# SENSORS_FMU_REV_1B.net
KiCad netlist of a schematic drawn in Altium Designer
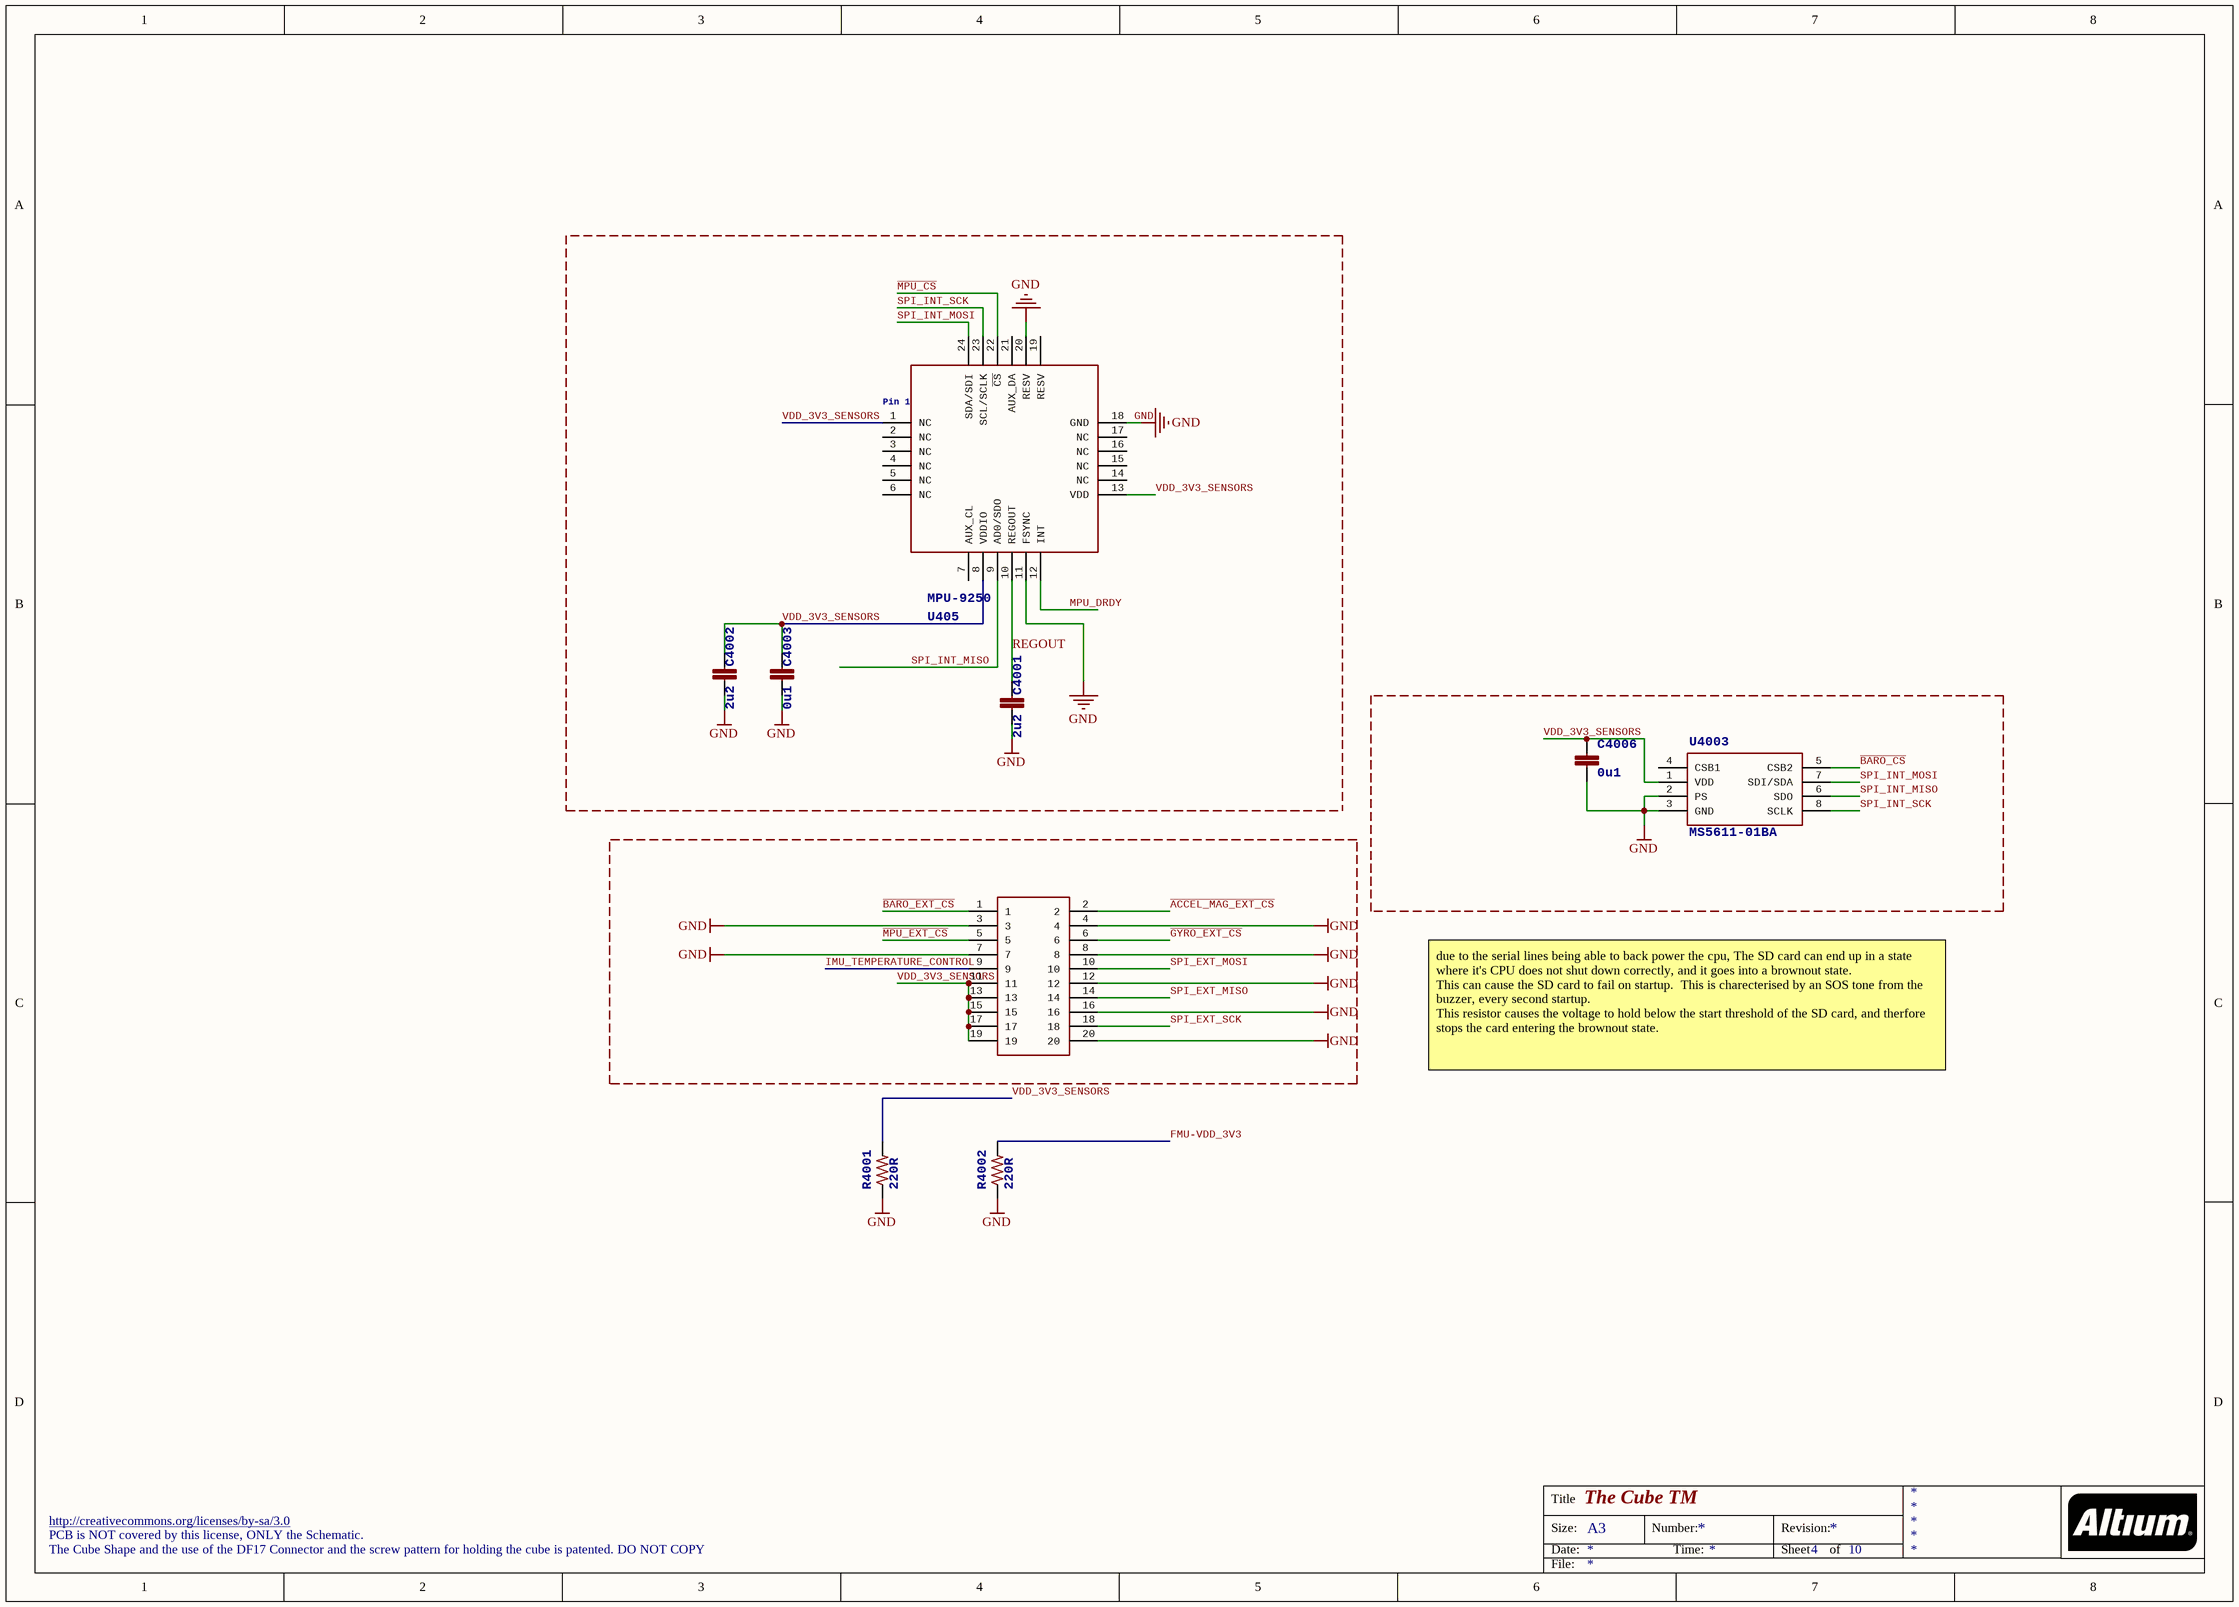
[diagram p0: SENSORS_FMU_REV_1B.SchDoc]

(export (version "E")
  (design (tool "Eeschema 10.0.6"))
  (components
    (comp (ref "C4001")
      (value "2u2")
      (footprint "0603-CAP")
      (description "CAP CER 2.2UF 16V 10% X6S 0603")
      (libsource (lib "pixhawk2") (part "CAP0603"))
    )
    (comp (ref "C4002")
      (value "2u2")
      (footprint "0603-CAP")
      (description "CAP CER 2.2UF 16V 10% X6S 0603")
      (libsource (lib "pixhawk2") (part "CAP0603"))
    )
    (comp (ref "C4003")
      (value "0u1")
      (footprint "0402-CAP")
      (description "CAP CER 0.1UF 16V Y5V 0402")
      (libsource (lib "pixhawk2") (part "CAP0402"))
    )
    (comp (ref "C4006")
      (value "0u1")
      (footprint "0402-CAP")
      (description "CAP CER 0.1UF 16V Y5V 0402")
      (libsource (lib "pixhawk2") (part "CAP0402"))
    )
    (comp (ref "R4001")
      (value "220R")
      (footprint "0402-RES")
      (description "RES 220 OHM 1/16W 1% 0402 SMD")
      (libsource (lib "pixhawk2") (part "RESISTOR0402-RES"))
    )
    (comp (ref "R4002")
      (value "220R")
      (footprint "0402-RES")
      (description "RES 220 OHM 1/16W 1% 0402 SMD")
      (libsource (lib "pixhawk2") (part "RESISTOR0402-RES"))
    )
    (comp (ref "U$2")
      (value "DF40C-20-DS")
      (footprint "DF-40C-20DS")
      (description "CONN RCPT 20POS 0.4MM SMD GOLD")
      (libsource (lib "pixhawk2") (part "DF40C-20-DS"))
    )
    (comp (ref "U405")
      (value "MPU-9250")
      (footprint "MPU-9250")
      (fields (field (name "PIN 1") "Pin 1"))
      (libsource (lib "pixhawk2") (part "MPU-6500"))
    )
    (comp (ref "U4003")
      (value "MS5611-01BA")
      (footprint "MS5611-01BA")
      (description "Board Mount Pressure Sensors")
      (libsource (lib "pixhawk2") (part "MS5611-01BA"))
    )
  )
  (nets
    (net (code "1") (name "/FMU-VDD_3V3") (class "Default")
      (node (ref "R4002") (pin "P$2") (pinfunction "2_P$2") (pintype "passive"))
    )
    (net (code "2") (name "/IMU_TEMPERATURE_CONTROL") (class "Default")
      (node (ref "U$2") (pin "9") (pinfunction "9_9") (pintype "passive"))
    )
    (net (code "3") (name "/MPU_DRDY") (class "Default")
      (node (ref "U405") (pin "12") (pinfunction "INT_12") (pintype "passive"))
    )
    (net (code "4") (name "/REGOUT") (class "Default")
      (node (ref "C4001") (pin "P$1") (pinfunction "1_P$1") (pintype "passive"))
      (node (ref "U405") (pin "10") (pinfunction "REGOUT_10") (pintype "passive"))
    )
    (net (code "5") (name "/SPI_EXT_MISO") (class "Default")
      (node (ref "U$2") (pin "14") (pinfunction "14_14") (pintype "passive"))
    )
    (net (code "6") (name "/SPI_EXT_MOSI") (class "Default")
      (node (ref "U$2") (pin "10") (pinfunction "10_10") (pintype "passive"))
    )
    (net (code "7") (name "/SPI_EXT_SCK") (class "Default")
      (node (ref "U$2") (pin "18") (pinfunction "18_18") (pintype "passive"))
    )
    (net (code "8") (name "/SPI_INT_MISO") (class "Default")
      (node (ref "U4003") (pin "6") (pinfunction "SDO_6") (pintype "passive"))
      (node (ref "U405") (pin "9") (pinfunction "AD0/SDO_9") (pintype "passive"))
    )
    (net (code "9") (name "/SPI_INT_MOSI") (class "Default")
      (node (ref "U4003") (pin "7") (pinfunction "SDI/SDA_7") (pintype "passive"))
      (node (ref "U405") (pin "24") (pinfunction "SDA/SDI_24") (pintype "passive"))
    )
    (net (code "10") (name "/SPI_INT_SCK") (class "Default")
      (node (ref "U4003") (pin "8") (pinfunction "SCLK_8") (pintype "passive"))
      (node (ref "U405") (pin "23") (pinfunction "SCL/SCLK_23") (pintype "passive"))
    )
    (net (code "11") (name "/VDD_3V3_SENSORS") (class "Default")
      (node (ref "C4002") (pin "P$1") (pinfunction "1_P$1") (pintype "passive"))
      (node (ref "C4003") (pin "P$1") (pinfunction "1_P$1") (pintype "passive"))
      (node (ref "C4006") (pin "P$1") (pinfunction "1_P$1") (pintype "passive"))
      (node (ref "R4001") (pin "P$2") (pinfunction "2_P$2") (pintype "passive"))
      (node (ref "U$2") (pin "11") (pinfunction "11_11") (pintype "passive"))
      (node (ref "U$2") (pin "13") (pinfunction "13_13") (pintype "passive"))
      (node (ref "U$2") (pin "15") (pinfunction "15_15") (pintype "passive"))
      (node (ref "U$2") (pin "17") (pinfunction "17_17") (pintype "passive"))
      (node (ref "U$2") (pin "19") (pinfunction "19_19") (pintype "passive"))
      (node (ref "U4003") (pin "1") (pinfunction "VDD_1") (pintype "passive"))
      (node (ref "U405") (pin "1") (pinfunction "NC_1") (pintype "passive"))
      (node (ref "U405") (pin "13") (pinfunction "VDD_13") (pintype "passive"))
      (node (ref "U405") (pin "8") (pinfunction "VDDIO_8") (pintype "passive"))
    )
    (net (code "12") (name "/~{ACCEL_MAG_EXT_CS}") (class "Default")
      (node (ref "U$2") (pin "2") (pinfunction "2_2") (pintype "passive"))
    )
    (net (code "13") (name "/~{BARO_CS}") (class "Default")
      (node (ref "U4003") (pin "5") (pinfunction "CSB2_5") (pintype "passive"))
    )
    (net (code "14") (name "/~{BARO_EXT_CS}") (class "Default")
      (node (ref "U$2") (pin "1") (pinfunction "1_1") (pintype "passive"))
    )
    (net (code "15") (name "/~{GYRO_EXT_CS}") (class "Default")
      (node (ref "U$2") (pin "6") (pinfunction "6_6") (pintype "passive"))
    )
    (net (code "16") (name "/~{MPU_CS}") (class "Default")
      (node (ref "U405") (pin "22") (pinfunction "~{CS}_22") (pintype "passive"))
    )
    (net (code "17") (name "/~{MPU_EXT_CS}") (class "Default")
      (node (ref "U$2") (pin "5") (pinfunction "5_5") (pintype "passive"))
    )
    (net (code "18") (name "GND") (class "Default")
      (node (ref "C4001") (pin "P$2") (pinfunction "2_P$2") (pintype "passive"))
      (node (ref "C4002") (pin "P$2") (pinfunction "2_P$2") (pintype "passive"))
      (node (ref "C4003") (pin "P$2") (pinfunction "2_P$2") (pintype "passive"))
      (node (ref "C4006") (pin "P$2") (pinfunction "2_P$2") (pintype "passive"))
      (node (ref "R4001") (pin "P$1") (pinfunction "1_P$1") (pintype "passive"))
      (node (ref "R4002") (pin "P$1") (pinfunction "1_P$1") (pintype "passive"))
      (node (ref "U$2") (pin "12") (pinfunction "12_12") (pintype "passive"))
      (node (ref "U$2") (pin "16") (pinfunction "16_16") (pintype "passive"))
      (node (ref "U$2") (pin "20") (pinfunction "20_20") (pintype "passive"))
      (node (ref "U$2") (pin "3") (pinfunction "3_3") (pintype "passive"))
      (node (ref "U$2") (pin "4") (pinfunction "4_4") (pintype "passive"))
      (node (ref "U$2") (pin "7") (pinfunction "7_7") (pintype "passive"))
      (node (ref "U$2") (pin "8") (pinfunction "8_8") (pintype "passive"))
      (node (ref "U4003") (pin "2") (pinfunction "PS_2") (pintype "passive"))
      (node (ref "U4003") (pin "3") (pinfunction "GND_3") (pintype "passive"))
      (node (ref "U405") (pin "11") (pinfunction "FSYNC_11") (pintype "passive"))
      (node (ref "U405") (pin "18") (pinfunction "GND_18") (pintype "passive"))
      (node (ref "U405") (pin "20") (pinfunction "RESV_20") (pintype "passive"))
    )
    (net (code "19") (name "unconnected-(U405-AUX_CL-Pad7)") (class "Default")
      (node (ref "U405") (pin "7") (pinfunction "AUX_CL_7") (pintype "passive"))
    )
    (net (code "20") (name "unconnected-(U405-AUX_DA-Pad21)") (class "Default")
      (node (ref "U405") (pin "21") (pinfunction "AUX_DA_21") (pintype "passive"))
    )
    (net (code "21") (name "unconnected-(U405-NC-Pad2)") (class "Default")
      (node (ref "U405") (pin "2") (pinfunction "NC_2") (pintype "passive"))
    )
    (net (code "22") (name "unconnected-(U405-NC-Pad3)") (class "Default")
      (node (ref "U405") (pin "3") (pinfunction "NC_3") (pintype "passive"))
    )
    (net (code "23") (name "unconnected-(U405-NC-Pad4)") (class "Default")
      (node (ref "U405") (pin "4") (pinfunction "NC_4") (pintype "passive"))
    )
    (net (code "24") (name "unconnected-(U405-NC-Pad5)") (class "Default")
      (node (ref "U405") (pin "5") (pinfunction "NC_5") (pintype "passive"))
    )
    (net (code "25") (name "unconnected-(U405-NC-Pad6)") (class "Default")
      (node (ref "U405") (pin "6") (pinfunction "NC_6") (pintype "passive"))
    )
    (net (code "26") (name "unconnected-(U405-NC-Pad14)") (class "Default")
      (node (ref "U405") (pin "14") (pinfunction "NC_14") (pintype "passive"))
    )
    (net (code "27") (name "unconnected-(U405-NC-Pad15)") (class "Default")
      (node (ref "U405") (pin "15") (pinfunction "NC_15") (pintype "passive"))
    )
    (net (code "28") (name "unconnected-(U405-NC-Pad16)") (class "Default")
      (node (ref "U405") (pin "16") (pinfunction "NC_16") (pintype "passive"))
    )
    (net (code "29") (name "unconnected-(U405-NC-Pad17)") (class "Default")
      (node (ref "U405") (pin "17") (pinfunction "NC_17") (pintype "passive"))
    )
    (net (code "30") (name "unconnected-(U405-RESV-Pad19)") (class "Default")
      (node (ref "U405") (pin "19") (pinfunction "RESV_19") (pintype "passive"))
    )
    (net (code "31") (name "unconnected-(U4003-CSB1-Pad4)") (class "Default")
      (node (ref "U4003") (pin "4") (pinfunction "CSB1_4") (pintype "passive"))
    )
  )
)
